# HubHub.net
KiCad netlist of a schematic drawn in Altium Designer
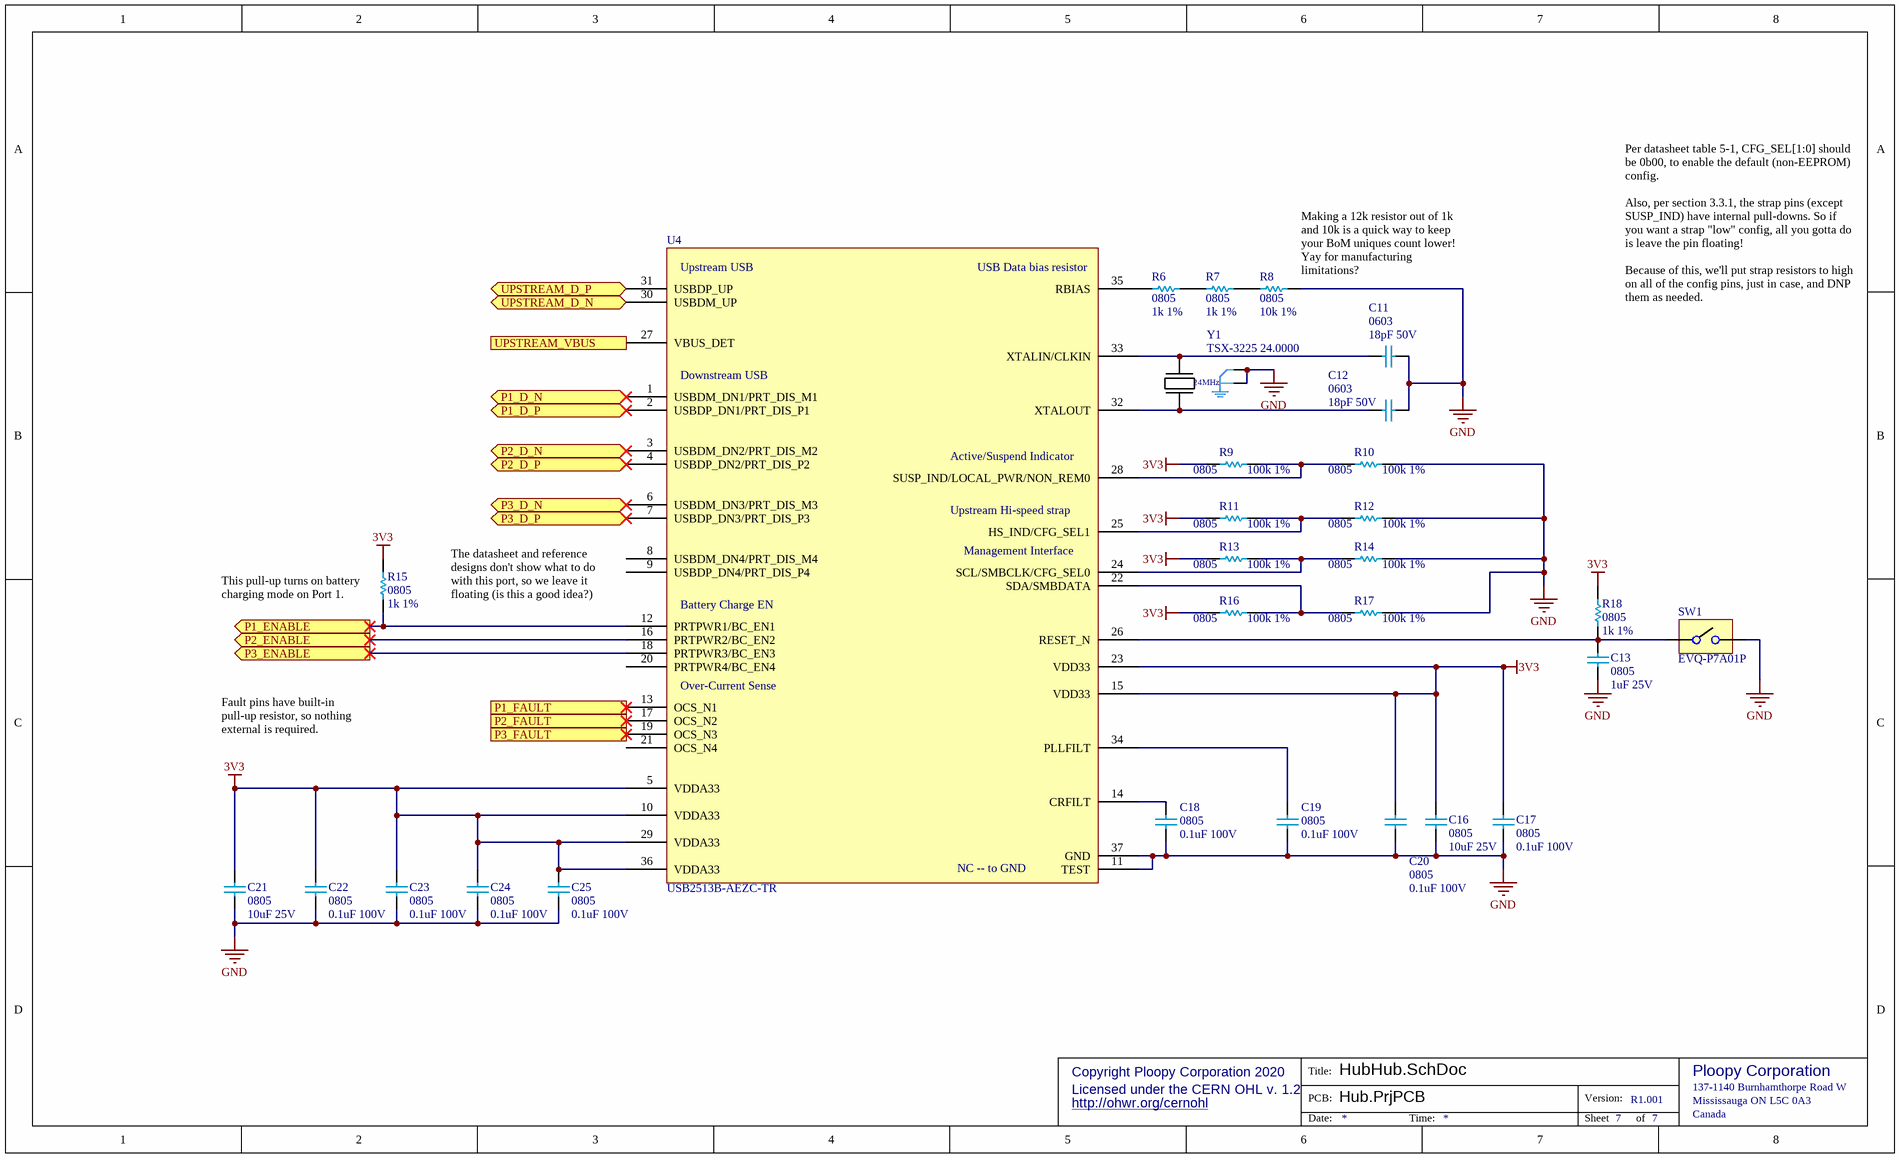
[diagram p0: HubHub.SchDoc]

(export (version "E")
  (design (tool "Eeschema 10.0.6"))
  (components
    (comp (ref "C11")
      (value "0603")
      (footprint "0603")
      (description "0603, C0G or better")
      (fields (field (name "ALTIUM_VALUE") "18pF 50V"))
      (libsource (lib "Chip_Passives") (part "Cap 18pF 50V"))
    )
    (comp (ref "C12")
      (value "0603")
      (footprint "0603")
      (description "0603, C0G or better")
      (fields (field (name "ALTIUM_VALUE") "18pF 50V"))
      (libsource (lib "Chip_Passives") (part "Cap 18pF 50V"))
    )
    (comp (ref "C13")
      (value "0805")
      (footprint "0805")
      (description "0805, X5R or better")
      (fields (field (name "ALTIUM_VALUE") "1uF 25V"))
      (libsource (lib "Chip_Passives") (part "Cap 1uF 25V"))
    )
    (comp (ref "C16")
      (value "0805")
      (footprint "0805")
      (description "0805, X5R or better")
      (fields (field (name "ALTIUM_VALUE") "10uF 25V"))
      (libsource (lib "Chip_Passives") (part "Cap 10uF 25V"))
    )
    (comp (ref "C17")
      (value "0805")
      (footprint "0805")
      (description "0805, X5R or better")
      (fields (field (name "ALTIUM_VALUE") "0.1uF 100V"))
      (libsource (lib "Chip_Passives") (part "Cap 0.1uF 100V"))
    )
    (comp (ref "C18")
      (value "0805")
      (footprint "0805")
      (description "0805, X5R or better")
      (fields (field (name "ALTIUM_VALUE") "0.1uF 100V"))
      (libsource (lib "Chip_Passives") (part "Cap 0.1uF 100V"))
    )
    (comp (ref "C19")
      (value "0805")
      (footprint "0805")
      (description "0805, X5R or better")
      (fields (field (name "ALTIUM_VALUE") "0.1uF 100V"))
      (libsource (lib "Chip_Passives") (part "Cap 0.1uF 100V"))
    )
    (comp (ref "C20")
      (value "0805")
      (footprint "0805")
      (description "0805, X5R or better")
      (fields (field (name "ALTIUM_VALUE") "0.1uF 100V"))
      (libsource (lib "Chip_Passives") (part "Cap 0.1uF 100V"))
    )
    (comp (ref "C21")
      (value "0805")
      (footprint "0805")
      (description "0805, X5R or better")
      (fields (field (name "ALTIUM_VALUE") "10uF 25V"))
      (libsource (lib "Chip_Passives") (part "Cap 10uF 25V"))
    )
    (comp (ref "C22")
      (value "0805")
      (footprint "0805")
      (description "0805, X5R or better")
      (fields (field (name "ALTIUM_VALUE") "0.1uF 100V"))
      (libsource (lib "Chip_Passives") (part "Cap 0.1uF 100V"))
    )
    (comp (ref "C23")
      (value "0805")
      (footprint "0805")
      (description "0805, X5R or better")
      (fields (field (name "ALTIUM_VALUE") "0.1uF 100V"))
      (libsource (lib "Chip_Passives") (part "Cap 0.1uF 100V"))
    )
    (comp (ref "C24")
      (value "0805")
      (footprint "0805")
      (description "0805, X5R or better")
      (fields (field (name "ALTIUM_VALUE") "0.1uF 100V"))
      (libsource (lib "Chip_Passives") (part "Cap 0.1uF 100V"))
    )
    (comp (ref "C25")
      (value "0805")
      (footprint "0805")
      (description "0805, X5R or better")
      (fields (field (name "ALTIUM_VALUE") "0.1uF 100V"))
      (libsource (lib "Chip_Passives") (part "Cap 0.1uF 100V"))
    )
    (comp (ref "R6")
      (value "0805")
      (footprint "0805")
      (description "Chip resistor, 1/8W 100PPM")
      (fields (field (name "ALTIUM_VALUE") "1k 1%"))
      (libsource (lib "Chip_Passives") (part "Res 1k 1% 0805"))
    )
    (comp (ref "R7")
      (value "0805")
      (footprint "0805")
      (description "Chip resistor, 1/8W 100PPM")
      (fields (field (name "ALTIUM_VALUE") "1k 1%"))
      (libsource (lib "Chip_Passives") (part "Res 1k 1% 0805"))
    )
    (comp (ref "R8")
      (value "0805")
      (footprint "0805")
      (description "Chip resistor")
      (fields (field (name "ALTIUM_VALUE") "10k 1%"))
      (libsource (lib "Chip_Passives") (part "Res 10k 1% 0805"))
    )
    (comp (ref "R9")
      (value "0805")
      (footprint "0805")
      (description "Chip resistor")
      (fields (field (name "ALTIUM_VALUE") "100k 1%"))
      (libsource (lib "Chip_Passives") (part "Res 100k 1% 0805"))
    )
    (comp (ref "R10")
      (value "0805")
      (footprint "0805")
      (description "Chip resistor")
      (fields (field (name "ALTIUM_VALUE") "100k 1%"))
      (libsource (lib "Chip_Passives") (part "Res 100k 1% 0805"))
    )
    (comp (ref "R11")
      (value "0805")
      (footprint "0805")
      (description "Chip resistor")
      (fields (field (name "ALTIUM_VALUE") "100k 1%"))
      (libsource (lib "Chip_Passives") (part "Res 100k 1% 0805"))
    )
    (comp (ref "R12")
      (value "0805")
      (footprint "0805")
      (description "Chip resistor")
      (fields (field (name "ALTIUM_VALUE") "100k 1%"))
      (libsource (lib "Chip_Passives") (part "Res 100k 1% 0805"))
    )
    (comp (ref "R13")
      (value "0805")
      (footprint "0805")
      (description "Chip resistor")
      (fields (field (name "ALTIUM_VALUE") "100k 1%"))
      (libsource (lib "Chip_Passives") (part "Res 100k 1% 0805"))
    )
    (comp (ref "R14")
      (value "0805")
      (footprint "0805")
      (description "Chip resistor")
      (fields (field (name "ALTIUM_VALUE") "100k 1%"))
      (libsource (lib "Chip_Passives") (part "Res 100k 1% 0805"))
    )
    (comp (ref "R15")
      (value "0805")
      (footprint "0805")
      (description "Chip resistor, 1/8W 100PPM")
      (fields (field (name "ALTIUM_VALUE") "1k 1%"))
      (libsource (lib "Chip_Passives") (part "Res 1k 1% 0805"))
    )
    (comp (ref "R16")
      (value "0805")
      (footprint "0805")
      (description "Chip resistor")
      (fields (field (name "ALTIUM_VALUE") "100k 1%"))
      (libsource (lib "Chip_Passives") (part "Res 100k 1% 0805"))
    )
    (comp (ref "R17")
      (value "0805")
      (footprint "0805")
      (description "Chip resistor")
      (fields (field (name "ALTIUM_VALUE") "100k 1%"))
      (libsource (lib "Chip_Passives") (part "Res 100k 1% 0805"))
    )
    (comp (ref "R18")
      (value "0805")
      (footprint "0805")
      (description "Chip resistor, 1/8W 100PPM")
      (fields (field (name "ALTIUM_VALUE") "1k 1%"))
      (libsource (lib "Chip_Passives") (part "Res 1k 1% 0805"))
    )
    (comp (ref "SW1")
      (value "EVQ-P7A01P")
      (footprint "EVQ-PQHB55")
      (description "Tactile Switches 3.5x2.9mm Right Ang Light Touch Switch")
      (libsource (lib "Switches") (part "EVQ-P7A01P"))
    )
    (comp (ref "U4")
      (value "USB2513B-AEZC-TR")
      (footprint "USB2513B - QFN50P600X600X100_HS-37M")
      (description "USB Hub Controller USB 2.0 USB Interface 36-QFN (6x6)")
      (libsource (lib "Connectivity") (part "USB2513B-AEZC-TR"))
    )
    (comp (ref "Y1")
      (value "TSX-3225 24.0000")
      (footprint "TSX-3225")
      (description "24MHz ±10ppm Crystal 9pF 40 Ohms 4-SMD, No Lead")
      (libsource (lib "Crystals") (part "TSX-3225 24.0000"))
    )
  )
  (nets
    (net (code "1") (name "/P1_D_N") (class "Default")
      (node (ref "U4") (pin "1") (pinfunction "USBDM_DN1/PRT_DIS_M1_1") (pintype "passive+no_connect"))
    )
    (net (code "2") (name "/P1_D_P") (class "Default")
      (node (ref "U4") (pin "2") (pinfunction "USBDP_DN1/PRT_DIS_P1_2") (pintype "passive+no_connect"))
    )
    (net (code "3") (name "/P1_ENABLE") (class "Default")
      (node (ref "R15") (pin "1") (pinfunction "1_1") (pintype "passive"))
      (node (ref "U4") (pin "12") (pinfunction "PRTPWR1/BC_EN1_12") (pintype "passive"))
    )
    (net (code "4") (name "/P1_FAULT") (class "Default")
      (node (ref "U4") (pin "13") (pinfunction "OCS_N1_13") (pintype "passive+no_connect"))
    )
    (net (code "5") (name "/P2_D_N") (class "Default")
      (node (ref "U4") (pin "3") (pinfunction "USBDM_DN2/PRT_DIS_M2_3") (pintype "passive+no_connect"))
    )
    (net (code "6") (name "/P2_D_P") (class "Default")
      (node (ref "U4") (pin "4") (pinfunction "USBDP_DN2/PRT_DIS_P2_4") (pintype "passive+no_connect"))
    )
    (net (code "7") (name "/P2_ENABLE") (class "Default")
      (node (ref "U4") (pin "16") (pinfunction "PRTPWR2/BC_EN2_16") (pintype "passive+no_connect"))
    )
    (net (code "8") (name "/P2_FAULT") (class "Default")
      (node (ref "U4") (pin "17") (pinfunction "OCS_N2_17") (pintype "passive+no_connect"))
    )
    (net (code "9") (name "/P3_D_N") (class "Default")
      (node (ref "U4") (pin "6") (pinfunction "USBDM_DN3/PRT_DIS_M3_6") (pintype "passive+no_connect"))
    )
    (net (code "10") (name "/P3_D_P") (class "Default")
      (node (ref "U4") (pin "7") (pinfunction "USBDP_DN3/PRT_DIS_P3_7") (pintype "passive+no_connect"))
    )
    (net (code "11") (name "/P3_ENABLE") (class "Default")
      (node (ref "U4") (pin "18") (pinfunction "PRTPWR3/BC_EN3_18") (pintype "passive+no_connect"))
    )
    (net (code "12") (name "/P3_FAULT") (class "Default")
      (node (ref "U4") (pin "19") (pinfunction "OCS_N3_19") (pintype "passive+no_connect"))
    )
    (net (code "13") (name "/UPSTREAM_D_N") (class "Default")
      (node (ref "U4") (pin "30") (pinfunction "USBDM_UP_30") (pintype "passive"))
    )
    (net (code "14") (name "/UPSTREAM_D_P") (class "Default")
      (node (ref "U4") (pin "31") (pinfunction "USBDP_UP_31") (pintype "passive"))
    )
    (net (code "15") (name "/UPSTREAM_VBUS") (class "Default")
      (node (ref "U4") (pin "27") (pinfunction "VBUS_DET_27") (pintype "passive"))
    )
    (net (code "16") (name "3V3") (class "Default")
      (node (ref "C16") (pin "2") (pinfunction "2_2") (pintype "passive"))
      (node (ref "C17") (pin "2") (pinfunction "2_2") (pintype "passive"))
      (node (ref "C20") (pin "2") (pinfunction "2_2") (pintype "passive"))
      (node (ref "C21") (pin "2") (pinfunction "2_2") (pintype "passive"))
      (node (ref "C22") (pin "2") (pinfunction "2_2") (pintype "passive"))
      (node (ref "C23") (pin "2") (pinfunction "2_2") (pintype "passive"))
      (node (ref "C24") (pin "2") (pinfunction "2_2") (pintype "passive"))
      (node (ref "C25") (pin "2") (pinfunction "2_2") (pintype "passive"))
      (node (ref "R11") (pin "1") (pinfunction "1_1") (pintype "passive"))
      (node (ref "R13") (pin "1") (pinfunction "1_1") (pintype "passive"))
      (node (ref "R15") (pin "2") (pinfunction "2_2") (pintype "passive"))
      (node (ref "R16") (pin "1") (pinfunction "1_1") (pintype "passive"))
      (node (ref "R18") (pin "2") (pinfunction "2_2") (pintype "passive"))
      (node (ref "R9") (pin "1") (pinfunction "1_1") (pintype "passive"))
      (node (ref "U4") (pin "10") (pinfunction "VDDA33_10") (pintype "passive"))
      (node (ref "U4") (pin "15") (pinfunction "VDD33_15") (pintype "passive"))
      (node (ref "U4") (pin "23") (pinfunction "VDD33_23") (pintype "passive"))
      (node (ref "U4") (pin "29") (pinfunction "VDDA33_29") (pintype "passive"))
      (node (ref "U4") (pin "36") (pinfunction "VDDA33_36") (pintype "passive"))
      (node (ref "U4") (pin "5") (pinfunction "VDDA33_5") (pintype "passive"))
    )
    (net (code "17") (name "GND") (class "Default")
      (node (ref "C11") (pin "1") (pinfunction "1_1") (pintype "passive"))
      (node (ref "C12") (pin "1") (pinfunction "1_1") (pintype "passive"))
      (node (ref "C13") (pin "1") (pinfunction "1_1") (pintype "passive"))
      (node (ref "C16") (pin "1") (pinfunction "1_1") (pintype "passive"))
      (node (ref "C17") (pin "1") (pinfunction "1_1") (pintype "passive"))
      (node (ref "C18") (pin "1") (pinfunction "1_1") (pintype "passive"))
      (node (ref "C19") (pin "1") (pinfunction "1_1") (pintype "passive"))
      (node (ref "C20") (pin "1") (pinfunction "1_1") (pintype "passive"))
      (node (ref "C21") (pin "1") (pinfunction "1_1") (pintype "passive"))
      (node (ref "C22") (pin "1") (pinfunction "1_1") (pintype "passive"))
      (node (ref "C23") (pin "1") (pinfunction "1_1") (pintype "passive"))
      (node (ref "C24") (pin "1") (pinfunction "1_1") (pintype "passive"))
      (node (ref "C25") (pin "1") (pinfunction "1_1") (pintype "passive"))
      (node (ref "R10") (pin "1") (pinfunction "1_1") (pintype "passive"))
      (node (ref "R12") (pin "1") (pinfunction "1_1") (pintype "passive"))
      (node (ref "R14") (pin "1") (pinfunction "1_1") (pintype "passive"))
      (node (ref "R17") (pin "1") (pinfunction "1_1") (pintype "passive"))
      (node (ref "R8") (pin "1") (pinfunction "1_1") (pintype "passive"))
      (node (ref "SW1") (pin "B") (pinfunction "B_B") (pintype "passive"))
      (node (ref "U4") (pin "11") (pinfunction "TEST_11") (pintype "passive"))
      (node (ref "U4") (pin "37") (pinfunction "GND_37") (pintype "passive"))
      (node (ref "Y1") (pin "2") (pinfunction "2_2") (pintype "passive"))
      (node (ref "Y1") (pin "4") (pinfunction "4_4") (pintype "passive"))
    )
    (net (code "18") (name "Net-(R6-Pad1)") (class "Default")
      (node (ref "R6") (pin "1") (pinfunction "1_1") (pintype "passive"))
      (node (ref "R7") (pin "2") (pinfunction "2_2") (pintype "passive"))
    )
    (net (code "19") (name "Net-(R7-Pad1)") (class "Default")
      (node (ref "R7") (pin "1") (pinfunction "1_1") (pintype "passive"))
      (node (ref "R8") (pin "2") (pinfunction "2_2") (pintype "passive"))
    )
    (net (code "20") (name "Net-(U4-CRFILT)") (class "Default")
      (node (ref "C18") (pin "2") (pinfunction "2_2") (pintype "passive"))
      (node (ref "U4") (pin "14") (pinfunction "CRFILT_14") (pintype "passive"))
    )
    (net (code "21") (name "Net-(U4-HS_IND{slash}CFG_SEL1)") (class "Default")
      (node (ref "R11") (pin "2") (pinfunction "2_2") (pintype "passive"))
      (node (ref "R12") (pin "2") (pinfunction "2_2") (pintype "passive"))
      (node (ref "U4") (pin "25") (pinfunction "HS_IND/CFG_SEL1_25") (pintype "passive"))
    )
    (net (code "22") (name "Net-(U4-PLLFILT)") (class "Default")
      (node (ref "C19") (pin "2") (pinfunction "2_2") (pintype "passive"))
      (node (ref "U4") (pin "34") (pinfunction "PLLFILT_34") (pintype "passive"))
    )
    (net (code "23") (name "Net-(U4-RBIAS)") (class "Default")
      (node (ref "R6") (pin "2") (pinfunction "2_2") (pintype "passive"))
      (node (ref "U4") (pin "35") (pinfunction "RBIAS_35") (pintype "passive"))
    )
    (net (code "24") (name "Net-(U4-RESET_N)") (class "Default")
      (node (ref "C13") (pin "2") (pinfunction "2_2") (pintype "passive"))
      (node (ref "R18") (pin "1") (pinfunction "1_1") (pintype "passive"))
      (node (ref "SW1") (pin "A") (pinfunction "A_A") (pintype "passive"))
      (node (ref "U4") (pin "26") (pinfunction "RESET_N_26") (pintype "passive"))
    )
    (net (code "25") (name "Net-(U4-SCL{slash}SMBCLK{slash}CFG_SEL0)") (class "Default")
      (node (ref "R13") (pin "2") (pinfunction "2_2") (pintype "passive"))
      (node (ref "R14") (pin "2") (pinfunction "2_2") (pintype "passive"))
      (node (ref "U4") (pin "24") (pinfunction "SCL/SMBCLK/CFG_SEL0_24") (pintype "passive"))
    )
    (net (code "26") (name "Net-(U4-SDA{slash}SMBDATA)") (class "Default")
      (node (ref "R16") (pin "2") (pinfunction "2_2") (pintype "passive"))
      (node (ref "R17") (pin "2") (pinfunction "2_2") (pintype "passive"))
      (node (ref "U4") (pin "22") (pinfunction "SDA/SMBDATA_22") (pintype "passive"))
    )
    (net (code "27") (name "Net-(U4-SUSP_IND{slash}LOCAL_PWR{slash}NON_REM0)") (class "Default")
      (node (ref "R10") (pin "2") (pinfunction "2_2") (pintype "passive"))
      (node (ref "R9") (pin "2") (pinfunction "2_2") (pintype "passive"))
      (node (ref "U4") (pin "28") (pinfunction "SUSP_IND/LOCAL_PWR/NON_REM0_28") (pintype "passive"))
    )
    (net (code "28") (name "Net-(U4-XTALIN{slash}CLKIN)") (class "Default")
      (node (ref "C11") (pin "2") (pinfunction "2_2") (pintype "passive"))
      (node (ref "U4") (pin "33") (pinfunction "XTALIN/CLKIN_33") (pintype "passive"))
      (node (ref "Y1") (pin "1") (pinfunction "1_1") (pintype "passive"))
    )
    (net (code "29") (name "Net-(U4-XTALOUT)") (class "Default")
      (node (ref "C12") (pin "2") (pinfunction "2_2") (pintype "passive"))
      (node (ref "U4") (pin "32") (pinfunction "XTALOUT_32") (pintype "passive"))
      (node (ref "Y1") (pin "3") (pinfunction "3_3") (pintype "passive"))
    )
    (net (code "30") (name "unconnected-(U4-OCS_N4-Pad21)") (class "Default")
      (node (ref "U4") (pin "21") (pinfunction "OCS_N4_21") (pintype "passive"))
    )
    (net (code "31") (name "unconnected-(U4-PRTPWR4{slash}BC_EN4-Pad20)") (class "Default")
      (node (ref "U4") (pin "20") (pinfunction "PRTPWR4/BC_EN4_20") (pintype "passive"))
    )
    (net (code "32") (name "unconnected-(U4-USBDM_DN4{slash}PRT_DIS_M4-Pad8)") (class "Default")
      (node (ref "U4") (pin "8") (pinfunction "USBDM_DN4/PRT_DIS_M4_8") (pintype "passive"))
    )
    (net (code "33") (name "unconnected-(U4-USBDP_DN4{slash}PRT_DIS_P4-Pad9)") (class "Default")
      (node (ref "U4") (pin "9") (pinfunction "USBDP_DN4/PRT_DIS_P4_9") (pintype "passive"))
    )
  )
)
